# SCH_ArduinoNanoOPL3_2022-04-20.net
KiCad netlist of a schematic drawn in EasyEDA
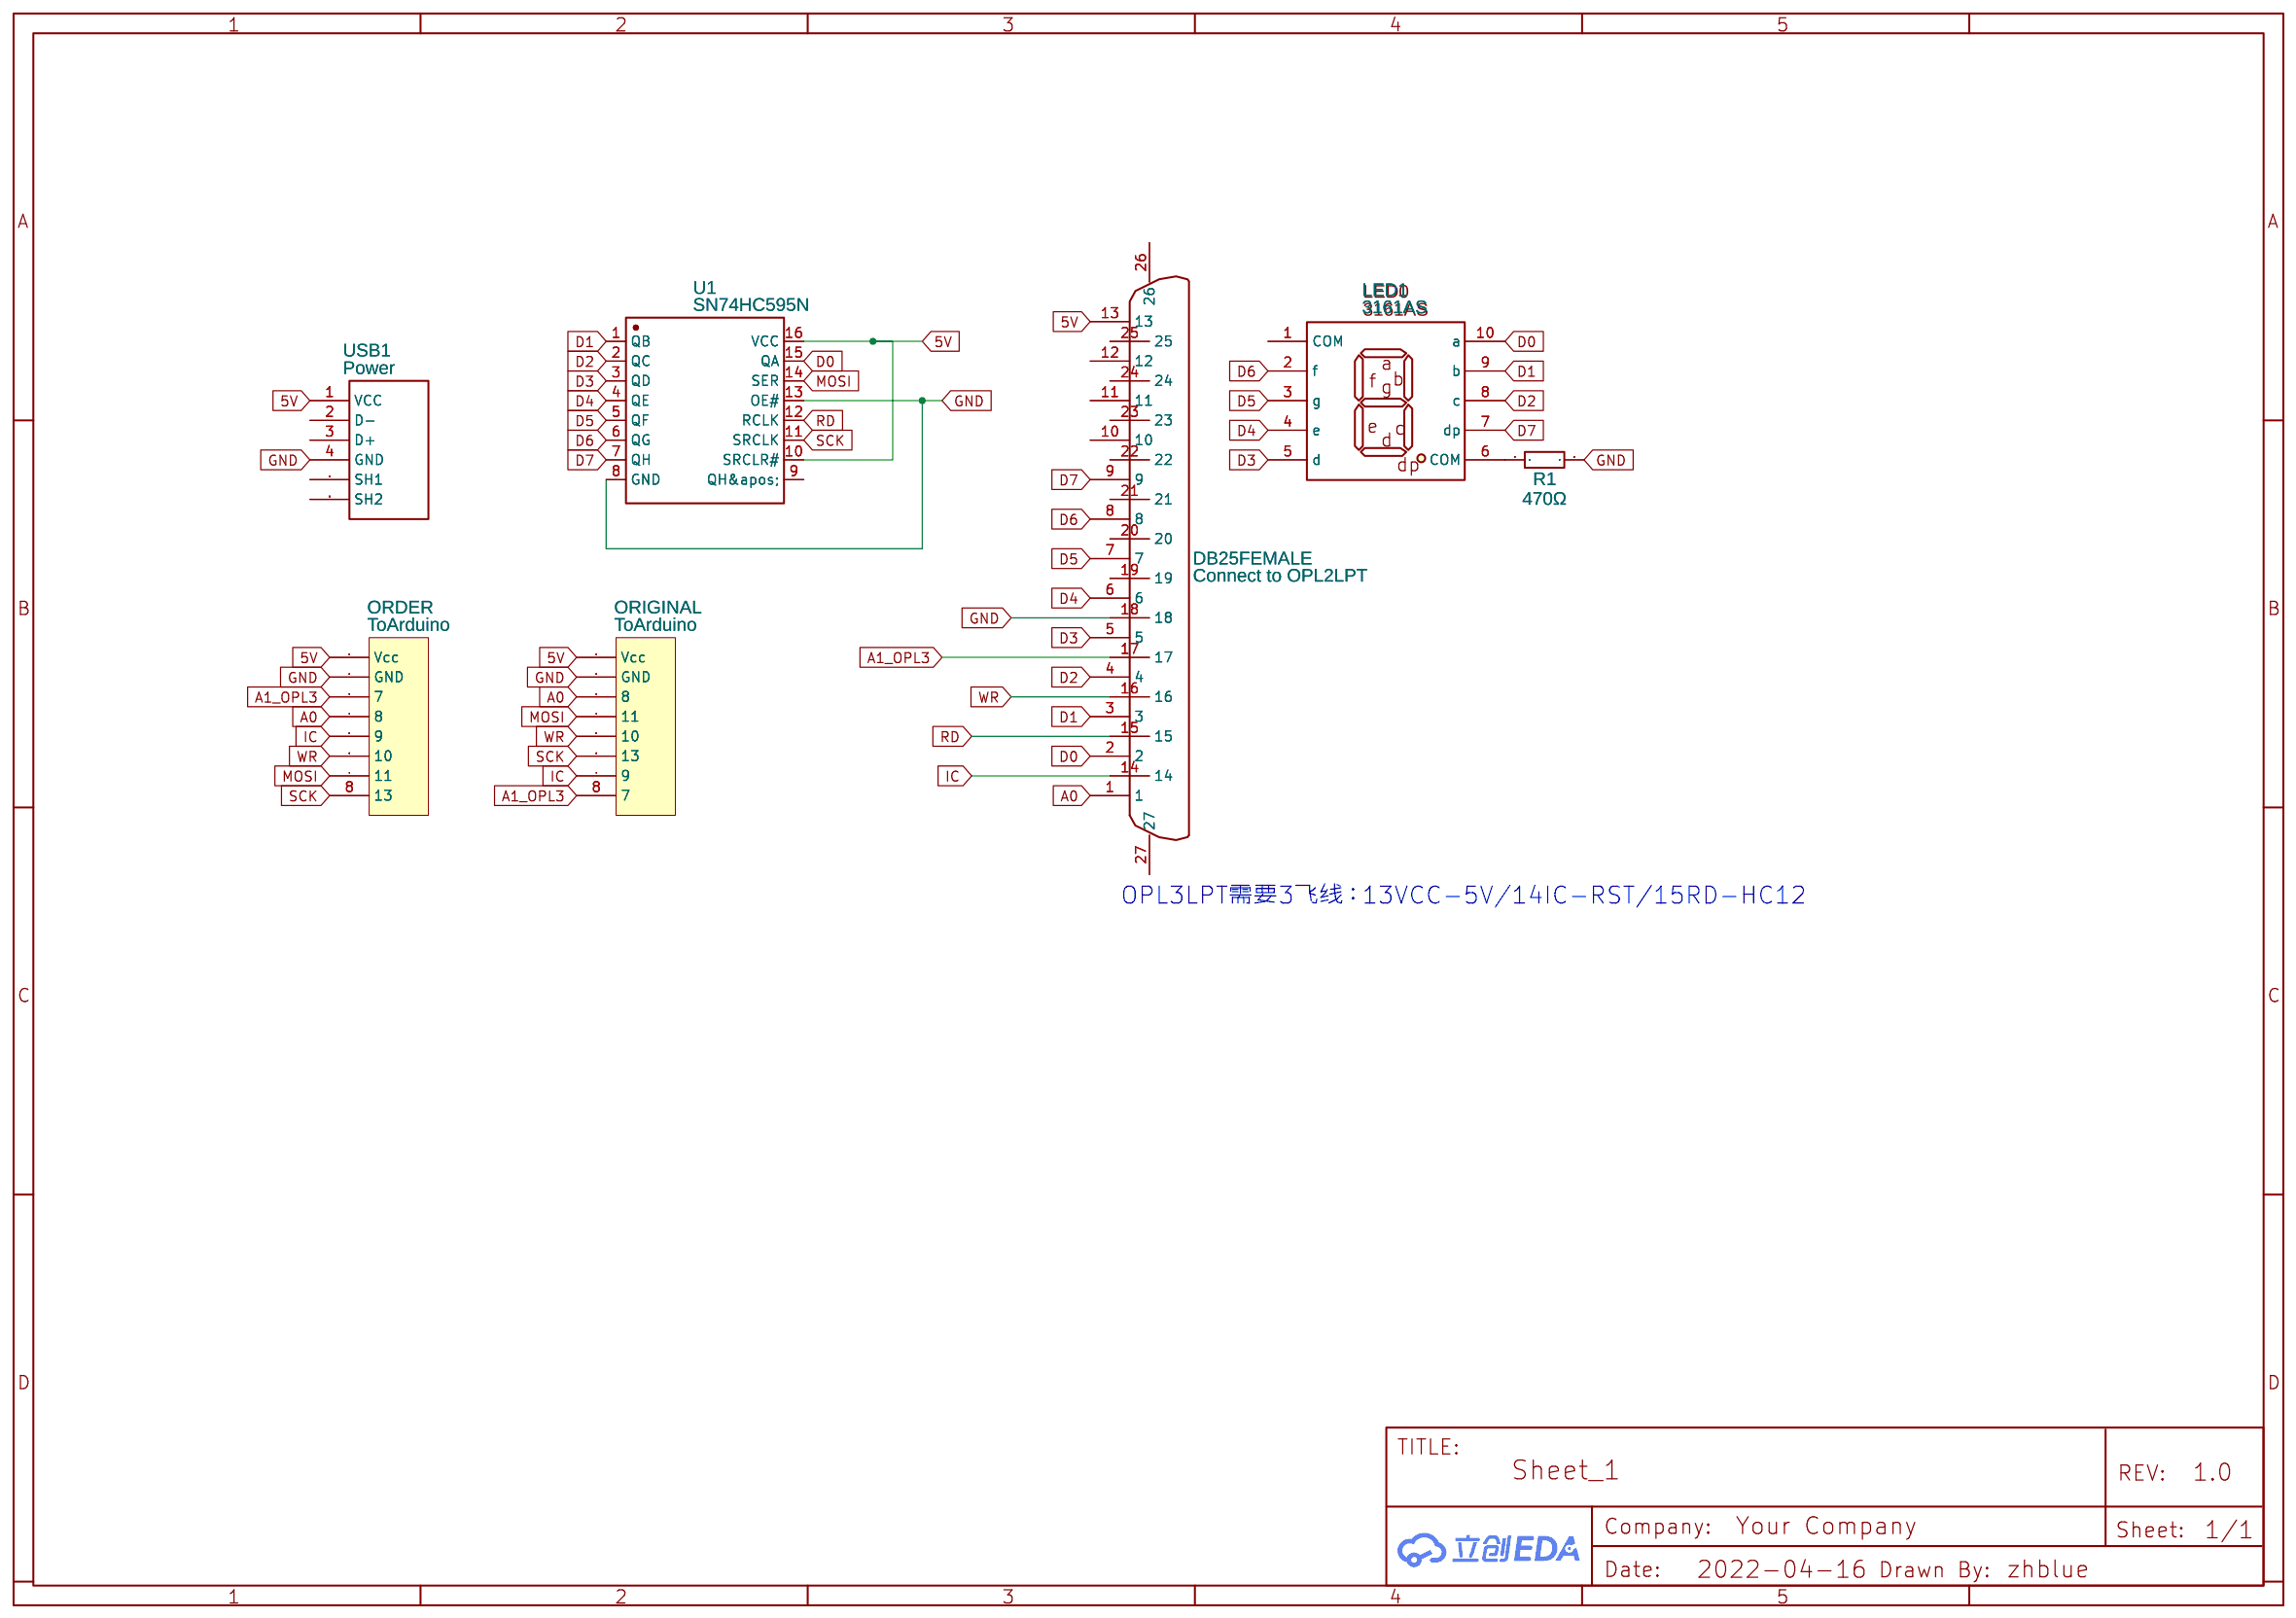
[diagram p0: schematic sheet]

(export (version "E")
  (design (tool "Eeschema 10.0.6"))
  (components
    (comp (ref "DB25FEMALE")
      (value "Connect to OPL2LPT")
      (fields
        (field (name "BOM_Manufacturer Part") "FDB2503-F0DS300K6KF")
        (field (name "BOM_Supplier Part") "C2834383")
      )
      (libsource (lib "") (part "FDB2503-F0DS300K6KF"))
    )
    (comp (ref "LED1") (value "3161AS") (libsource (lib "") (part "3161AS")))
    (comp (ref "ORDER") (value "ToArduino") (libsource (lib "") (part "8P")))
    (comp (ref "ORIGINAL") (value "ToArduino") (libsource (lib "") (part "8P_1")))
    (comp (ref "R1")
      (value "470Ω")
      (fields
        (field (name "BOM_Manufacturer Part") "QR0603F470RP05")
        (field (name "BOM_Supplier Part") "C176130")
      )
      (libsource (lib "") (part "QR0603F470RP05"))
    )
    (comp (ref "U1")
      (value "SN74HC595N")
      (fields (field (name "BOM_Supplier Part") "C78711"))
      (libsource (lib "") (part "SN74HC595N"))
    )
    (comp (ref "USB1")
      (value "Power")
      (fields
        (field (name "BOM_Manufacturer Part") "U-USBAR04P-F000")
        (field (name "BOM_Supplier Part") "C386740")
      )
      (libsource (lib "") (part "U-USBAR04P-F000"))
    )
  )
  (nets
    (net (code "1") (name "5V") (class "Default")
      (node (ref "DB25FEMALE") (pin "13") (pinfunction "13_13") (pintype "unspecified"))
      (node (ref "ORDER") (pin "1") (pinfunction "Vcc_1") (pintype "unspecified"))
      (node (ref "ORIGINAL") (pin "1") (pinfunction "Vcc_1") (pintype "unspecified"))
      (node (ref "U1") (pin "10") (pinfunction "SRCLR#_10") (pintype "unspecified"))
      (node (ref "U1") (pin "16") (pinfunction "VCC_16") (pintype "unspecified"))
      (node (ref "USB1") (pin "1") (pinfunction "VCC_1") (pintype "unspecified"))
    )
    (net (code "2") (name "A0") (class "Default")
      (node (ref "DB25FEMALE") (pin "1") (pinfunction "1_1") (pintype "unspecified"))
      (node (ref "ORDER") (pin "4") (pinfunction "8_4") (pintype "unspecified"))
      (node (ref "ORIGINAL") (pin "3") (pinfunction "8_3") (pintype "unspecified"))
    )
    (net (code "3") (name "A1_OPL3") (class "Default")
      (node (ref "DB25FEMALE") (pin "17") (pinfunction "17_17") (pintype "unspecified"))
      (node (ref "ORDER") (pin "3") (pinfunction "7_3") (pintype "unspecified"))
      (node (ref "ORIGINAL") (pin "8") (pinfunction "7_8") (pintype "unspecified"))
    )
    (net (code "4") (name "D0") (class "Default")
      (node (ref "DB25FEMALE") (pin "2") (pinfunction "2_2") (pintype "unspecified"))
      (node (ref "LED1") (pin "10") (pinfunction "a_10") (pintype "input"))
      (node (ref "U1") (pin "15") (pinfunction "QA_15") (pintype "unspecified"))
    )
    (net (code "5") (name "D1") (class "Default")
      (node (ref "DB25FEMALE") (pin "3") (pinfunction "3_3") (pintype "unspecified"))
      (node (ref "LED1") (pin "9") (pinfunction "b_9") (pintype "input"))
      (node (ref "U1") (pin "1") (pinfunction "QB_1") (pintype "unspecified"))
    )
    (net (code "6") (name "D2") (class "Default")
      (node (ref "DB25FEMALE") (pin "4") (pinfunction "4_4") (pintype "unspecified"))
      (node (ref "LED1") (pin "8") (pinfunction "c_8") (pintype "input"))
      (node (ref "U1") (pin "2") (pinfunction "QC_2") (pintype "unspecified"))
    )
    (net (code "7") (name "D3") (class "Default")
      (node (ref "DB25FEMALE") (pin "5") (pinfunction "5_5") (pintype "unspecified"))
      (node (ref "LED1") (pin "5") (pinfunction "d_5") (pintype "input"))
      (node (ref "U1") (pin "3") (pinfunction "QD_3") (pintype "unspecified"))
    )
    (net (code "8") (name "D4") (class "Default")
      (node (ref "DB25FEMALE") (pin "6") (pinfunction "6_6") (pintype "unspecified"))
      (node (ref "LED1") (pin "4") (pinfunction "e_4") (pintype "input"))
      (node (ref "U1") (pin "4") (pinfunction "QE_4") (pintype "unspecified"))
    )
    (net (code "9") (name "D5") (class "Default")
      (node (ref "DB25FEMALE") (pin "7") (pinfunction "7_7") (pintype "unspecified"))
      (node (ref "LED1") (pin "3") (pinfunction "g_3") (pintype "input"))
      (node (ref "U1") (pin "5") (pinfunction "QF_5") (pintype "unspecified"))
    )
    (net (code "10") (name "D6") (class "Default")
      (node (ref "DB25FEMALE") (pin "8") (pinfunction "8_8") (pintype "unspecified"))
      (node (ref "LED1") (pin "2") (pinfunction "f_2") (pintype "input"))
      (node (ref "U1") (pin "6") (pinfunction "QG_6") (pintype "unspecified"))
    )
    (net (code "11") (name "D7") (class "Default")
      (node (ref "DB25FEMALE") (pin "9") (pinfunction "9_9") (pintype "unspecified"))
      (node (ref "LED1") (pin "7") (pinfunction "dp_7") (pintype "input"))
      (node (ref "U1") (pin "7") (pinfunction "QH_7") (pintype "unspecified"))
    )
    (net (code "12") (name "GND") (class "Default")
      (node (ref "DB25FEMALE") (pin "18") (pinfunction "18_18") (pintype "unspecified"))
      (node (ref "ORDER") (pin "2") (pinfunction "GND_2") (pintype "unspecified"))
      (node (ref "ORIGINAL") (pin "2") (pinfunction "GND_2") (pintype "unspecified"))
      (node (ref "R1") (pin "2") (pinfunction "2_2") (pintype "unspecified"))
      (node (ref "U1") (pin "13") (pinfunction "OE#_13") (pintype "unspecified"))
      (node (ref "U1") (pin "8") (pinfunction "GND_8") (pintype "unspecified"))
      (node (ref "USB1") (pin "4") (pinfunction "GND_4") (pintype "unspecified"))
    )
    (net (code "13") (name "IC") (class "Default")
      (node (ref "DB25FEMALE") (pin "14") (pinfunction "14_14") (pintype "unspecified"))
      (node (ref "ORDER") (pin "5") (pinfunction "9_5") (pintype "unspecified"))
      (node (ref "ORIGINAL") (pin "7") (pinfunction "9_7") (pintype "unspecified"))
    )
    (net (code "14") (name "MOSI") (class "Default")
      (node (ref "ORDER") (pin "7") (pinfunction "11_7") (pintype "unspecified"))
      (node (ref "ORIGINAL") (pin "4") (pinfunction "11_4") (pintype "unspecified"))
      (node (ref "U1") (pin "14") (pinfunction "SER_14") (pintype "unspecified"))
    )
    (net (code "15") (name "Net-(LED1-COM-Pad6)") (class "Default")
      (node (ref "LED1") (pin "6") (pinfunction "COM_6") (pintype "input"))
      (node (ref "R1") (pin "1") (pinfunction "1_1") (pintype "unspecified"))
    )
    (net (code "16") (name "RD") (class "Default")
      (node (ref "DB25FEMALE") (pin "15") (pinfunction "15_15") (pintype "unspecified"))
      (node (ref "U1") (pin "12") (pinfunction "RCLK_12") (pintype "unspecified"))
    )
    (net (code "17") (name "SCK") (class "Default")
      (node (ref "ORDER") (pin "8") (pinfunction "13_8") (pintype "unspecified"))
      (node (ref "ORIGINAL") (pin "6") (pinfunction "13_6") (pintype "unspecified"))
      (node (ref "U1") (pin "11") (pinfunction "SRCLK_11") (pintype "unspecified"))
    )
    (net (code "18") (name "WR") (class "Default")
      (node (ref "DB25FEMALE") (pin "16") (pinfunction "16_16") (pintype "unspecified"))
      (node (ref "ORDER") (pin "6") (pinfunction "10_6") (pintype "unspecified"))
      (node (ref "ORIGINAL") (pin "5") (pinfunction "10_5") (pintype "unspecified"))
    )
    (net (code "19") (name "unconnected-(DB25FEMALE-Pad10)") (class "Default")
      (node (ref "DB25FEMALE") (pin "10") (pinfunction "10_10") (pintype "unspecified"))
    )
    (net (code "20") (name "unconnected-(DB25FEMALE-Pad11)") (class "Default")
      (node (ref "DB25FEMALE") (pin "11") (pinfunction "11_11") (pintype "unspecified"))
    )
    (net (code "21") (name "unconnected-(DB25FEMALE-Pad12)") (class "Default")
      (node (ref "DB25FEMALE") (pin "12") (pinfunction "12_12") (pintype "unspecified"))
    )
    (net (code "22") (name "unconnected-(DB25FEMALE-Pad19)") (class "Default")
      (node (ref "DB25FEMALE") (pin "19") (pinfunction "19_19") (pintype "unspecified"))
    )
    (net (code "23") (name "unconnected-(DB25FEMALE-Pad20)") (class "Default")
      (node (ref "DB25FEMALE") (pin "20") (pinfunction "20_20") (pintype "unspecified"))
    )
    (net (code "24") (name "unconnected-(DB25FEMALE-Pad21)") (class "Default")
      (node (ref "DB25FEMALE") (pin "21") (pinfunction "21_21") (pintype "unspecified"))
    )
    (net (code "25") (name "unconnected-(DB25FEMALE-Pad22)") (class "Default")
      (node (ref "DB25FEMALE") (pin "22") (pinfunction "22_22") (pintype "unspecified"))
    )
    (net (code "26") (name "unconnected-(DB25FEMALE-Pad23)") (class "Default")
      (node (ref "DB25FEMALE") (pin "23") (pinfunction "23_23") (pintype "unspecified"))
    )
    (net (code "27") (name "unconnected-(DB25FEMALE-Pad24)") (class "Default")
      (node (ref "DB25FEMALE") (pin "24") (pinfunction "24_24") (pintype "unspecified"))
    )
    (net (code "28") (name "unconnected-(DB25FEMALE-Pad25)") (class "Default")
      (node (ref "DB25FEMALE") (pin "25") (pinfunction "25_25") (pintype "unspecified"))
    )
    (net (code "29") (name "unconnected-(DB25FEMALE-Pad26)") (class "Default")
      (node (ref "DB25FEMALE") (pin "26") (pinfunction "26_26") (pintype "unspecified"))
    )
    (net (code "30") (name "unconnected-(DB25FEMALE-Pad27)") (class "Default")
      (node (ref "DB25FEMALE") (pin "27") (pinfunction "27_27") (pintype "unspecified"))
    )
    (net (code "31") (name "unconnected-(LED1-COM-Pad1)") (class "Default")
      (node (ref "LED1") (pin "1") (pinfunction "COM_1") (pintype "input"))
    )
    (net (code "32") (name "unconnected-(U1-QH&apos;-Pad9)") (class "Default")
      (node (ref "U1") (pin "9") (pinfunction "QH&apos;_9") (pintype "unspecified"))
    )
    (net (code "33") (name "unconnected-(USB1-D+-Pad3)") (class "Default")
      (node (ref "USB1") (pin "3") (pinfunction "D+_3") (pintype "unspecified"))
    )
    (net (code "34") (name "unconnected-(USB1-D--Pad2)") (class "Default")
      (node (ref "USB1") (pin "2") (pinfunction "D-_2") (pintype "unspecified"))
    )
    (net (code "35") (name "unconnected-(USB1-SH1-Pad5)") (class "Default")
      (node (ref "USB1") (pin "5") (pinfunction "SH1_5") (pintype "unspecified"))
    )
    (net (code "36") (name "unconnected-(USB1-SH2-Pad6)") (class "Default")
      (node (ref "USB1") (pin "6") (pinfunction "SH2_6") (pintype "unspecified"))
    )
  )
)
